# ESP-WROOM-32-Breakout.net
KiCad netlist of a schematic drawn in EAGLE
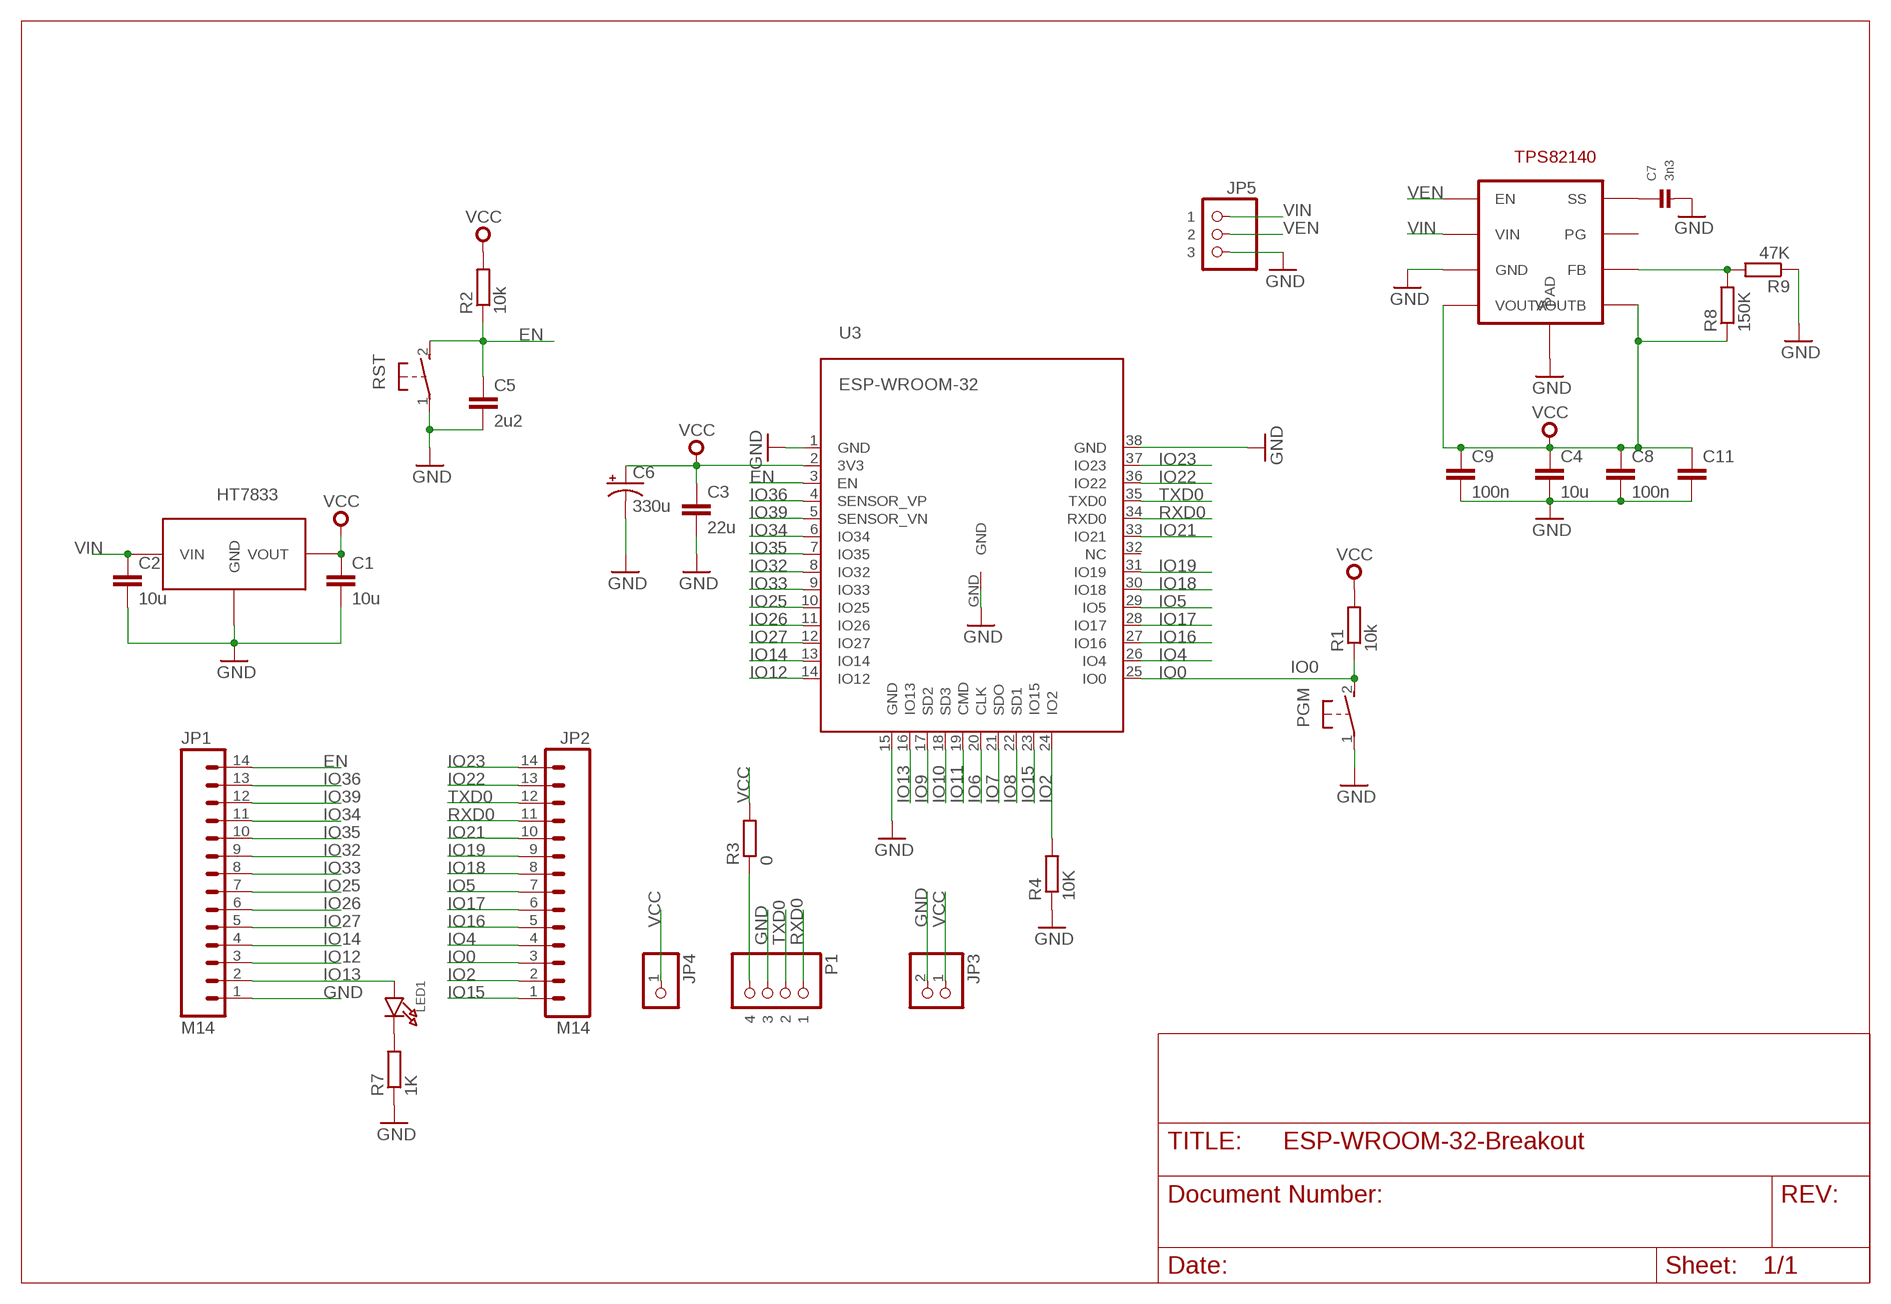
[diagram p0: schematic, sheet 1]

(export (version "E")
  (design (tool "Eeschema 10.0.6"))
  (components
    (comp (ref "C1")
      (value "10u")
      (footprint "eagle-import:C0603")
      (libsource (lib "eagle-import") (part "C-EUC0603"))
    )
    (comp (ref "C2")
      (value "10u")
      (footprint "eagle-import:C0603")
      (libsource (lib "eagle-import") (part "C-EUC0603"))
    )
    (comp (ref "C3")
      (value "22u")
      (footprint "eagle-import:0805")
      (libsource (lib "eagle-import") (part "CAP0805"))
    )
    (comp (ref "C4")
      (value "10u")
      (footprint "eagle-import:C0603")
      (libsource (lib "eagle-import") (part "C-EUC0603"))
    )
    (comp (ref "C5")
      (value "2u2")
      (footprint "eagle-import:C0603")
      (libsource (lib "eagle-import") (part "C-EUC0603"))
    )
    (comp (ref "C6")
      (value "330u")
      (footprint "eagle-import:VISHAY_C")
      (libsource (lib "eagle-import") (part "CAP_POLSMD"))
    )
    (comp (ref "C7")
      (value "3n3")
      (footprint "eagle-import:0603")
      (libsource (lib "eagle-import") (part "CAP_CERAMIC0603"))
    )
    (comp (ref "C8")
      (value "100n")
      (footprint "eagle-import:C0603")
      (libsource (lib "eagle-import") (part "C-EUC0603"))
    )
    (comp (ref "C9")
      (value "100n")
      (footprint "eagle-import:C0603")
      (libsource (lib "eagle-import") (part "C-EUC0603"))
    )
    (comp (ref "C11")
      (value "CAPSMD")
      (footprint "eagle-import:GRM43D")
      (libsource (lib "eagle-import") (part "CAPSMD"))
    )
    (comp (ref "JP1")
      (value "M14")
      (footprint "eagle-import:1X14")
      (libsource (lib "eagle-import") (part "M14"))
    )
    (comp (ref "JP2")
      (value "M14")
      (footprint "eagle-import:1X14")
      (libsource (lib "eagle-import") (part "M14"))
    )
    (comp (ref "JP3")
      (value "HEADER-1X2ROUND")
      (footprint "eagle-import:1X02_ROUND")
      (libsource (lib "eagle-import") (part "HEADER-1X2ROUND"))
    )
    (comp (ref "JP4")
      (value "HEADER-1X1ROUND")
      (footprint "eagle-import:1X01_ROUND")
      (libsource (lib "eagle-import") (part "HEADER-1X1ROUND"))
    )
    (comp (ref "JP5")
      (value "HEADER-1X3ROUND")
      (footprint "eagle-import:1X03_ROUND")
      (libsource (lib "eagle-import") (part "HEADER-1X3ROUND"))
    )
    (comp (ref "LED1")
      (value "LED0603")
      (footprint "eagle-import:CHIPLED_0603")
      (libsource (lib "eagle-import") (part "LED0603"))
    )
    (comp (ref "P1")
      (value "HEADER-1X4ROUND")
      (footprint "eagle-import:1X04_ROUND")
      (libsource (lib "eagle-import") (part "HEADER-1X4ROUND"))
    )
    (comp (ref "PGM")
      (value "DTSM-3")
      (footprint "eagle-import:DTSM-3")
      (libsource (lib "eagle-import") (part "DTSM-3"))
    )
    (comp (ref "R1")
      (value "10k")
      (footprint "eagle-import:R0603")
      (libsource (lib "eagle-import") (part "R-EU_R0603"))
    )
    (comp (ref "R2")
      (value "10k")
      (footprint "eagle-import:R0603")
      (libsource (lib "eagle-import") (part "R-EU_R0603"))
    )
    (comp (ref "R3")
      (value "0")
      (footprint "eagle-import:R0603")
      (libsource (lib "eagle-import") (part "R-EU_R0603"))
    )
    (comp (ref "R4")
      (value "10K")
      (footprint "eagle-import:R0603")
      (libsource (lib "eagle-import") (part "R-EU_R0603"))
    )
    (comp (ref "R7")
      (value "1K")
      (footprint "eagle-import:R0603")
      (libsource (lib "eagle-import") (part "R-EU_R0603"))
    )
    (comp (ref "R8")
      (value "150K")
      (footprint "eagle-import:R0603")
      (libsource (lib "eagle-import") (part "R-EU_R0603"))
    )
    (comp (ref "R9")
      (value "47K")
      (footprint "eagle-import:R0603")
      (libsource (lib "eagle-import") (part "R-EU_R0603"))
    )
    (comp (ref "RST")
      (value "DTSM-3")
      (footprint "eagle-import:DTSM-3")
      (libsource (lib "eagle-import") (part "DTSM-3"))
    )
    (comp (ref "U$1")
      (value "HT7833")
      (footprint "eagle-import:SOT89")
      (libsource (lib "eagle-import") (part "HT7333"))
    )
    (comp (ref "U$2")
      (value "TPS82140")
      (footprint "eagle-import:TPS82140")
      (libsource (lib "eagle-import") (part "TPS82140"))
    )
    (comp (ref "U3")
      (value "ESP-WROOM-32")
      (footprint "eagle-import:ESP-WROOM-32")
      (libsource (lib "eagle-import") (part "ESP-WROOM-32"))
    )
  )
  (nets
    (net (code "1") (name "/EN") (class "Default")
      (node (ref "C5") (pin "1") (pinfunction "1_1") (pintype "passive"))
      (node (ref "JP1") (pin "14") (pinfunction "14_14") (pintype "passive"))
      (node (ref "R2") (pin "1") (pinfunction "1_1") (pintype "passive"))
      (node (ref "RST") (pin "2") (pinfunction "2_2") (pintype "passive"))
      (node (ref "U3") (pin "3") (pinfunction "EN_3") (pintype "bidirectional"))
    )
    (net (code "2") (name "/IO0") (class "Default")
      (node (ref "JP2") (pin "3") (pinfunction "3_3") (pintype "passive"))
      (node (ref "PGM") (pin "2") (pinfunction "2_2") (pintype "passive"))
      (node (ref "R1") (pin "1") (pinfunction "1_1") (pintype "passive"))
      (node (ref "U3") (pin "25") (pinfunction "IO0_25") (pintype "bidirectional"))
    )
    (net (code "3") (name "/IO2") (class "Default")
      (node (ref "JP2") (pin "2") (pinfunction "2_2") (pintype "passive"))
      (node (ref "R4") (pin "2") (pinfunction "2_2") (pintype "passive"))
      (node (ref "U3") (pin "24") (pinfunction "IO2_24") (pintype "bidirectional"))
    )
    (net (code "4") (name "/IO4") (class "Default")
      (node (ref "JP2") (pin "4") (pinfunction "4_4") (pintype "passive"))
      (node (ref "U3") (pin "26") (pinfunction "IO4_26") (pintype "bidirectional"))
    )
    (net (code "5") (name "/IO5") (class "Default")
      (node (ref "JP2") (pin "7") (pinfunction "7_7") (pintype "passive"))
      (node (ref "U3") (pin "29") (pinfunction "IO5_29") (pintype "bidirectional"))
    )
    (net (code "6") (name "/IO6") (class "Default")
      (node (ref "U3") (pin "20") (pinfunction "CLK_20") (pintype "bidirectional"))
    )
    (net (code "7") (name "/IO7") (class "Default")
      (node (ref "U3") (pin "21") (pinfunction "SDO_21") (pintype "bidirectional"))
    )
    (net (code "8") (name "/IO8") (class "Default")
      (node (ref "U3") (pin "22") (pinfunction "SD1_22") (pintype "bidirectional"))
    )
    (net (code "9") (name "/IO9") (class "Default")
      (node (ref "U3") (pin "17") (pinfunction "SD2_17") (pintype "bidirectional"))
    )
    (net (code "10") (name "/IO10") (class "Default")
      (node (ref "U3") (pin "18") (pinfunction "SD3_18") (pintype "bidirectional"))
    )
    (net (code "11") (name "/IO11") (class "Default")
      (node (ref "U3") (pin "19") (pinfunction "CMD_19") (pintype "bidirectional"))
    )
    (net (code "12") (name "/IO12") (class "Default")
      (node (ref "JP1") (pin "3") (pinfunction "3_3") (pintype "passive"))
      (node (ref "U3") (pin "14") (pinfunction "IO12_14") (pintype "bidirectional"))
    )
    (net (code "13") (name "/IO13") (class "Default")
      (node (ref "JP1") (pin "2") (pinfunction "2_2") (pintype "passive"))
      (node (ref "LED1") (pin "A") (pinfunction "A_A") (pintype "passive"))
      (node (ref "U3") (pin "16") (pinfunction "IO13_16") (pintype "bidirectional"))
    )
    (net (code "14") (name "/IO14") (class "Default")
      (node (ref "JP1") (pin "4") (pinfunction "4_4") (pintype "passive"))
      (node (ref "U3") (pin "13") (pinfunction "IO14_13") (pintype "bidirectional"))
    )
    (net (code "15") (name "/IO15") (class "Default")
      (node (ref "JP2") (pin "1") (pinfunction "1_1") (pintype "passive"))
      (node (ref "U3") (pin "23") (pinfunction "IO15_23") (pintype "bidirectional"))
    )
    (net (code "16") (name "/IO16") (class "Default")
      (node (ref "JP2") (pin "5") (pinfunction "5_5") (pintype "passive"))
      (node (ref "U3") (pin "27") (pinfunction "IO16_27") (pintype "bidirectional"))
    )
    (net (code "17") (name "/IO17") (class "Default")
      (node (ref "JP2") (pin "6") (pinfunction "6_6") (pintype "passive"))
      (node (ref "U3") (pin "28") (pinfunction "IO17_28") (pintype "bidirectional"))
    )
    (net (code "18") (name "/IO18") (class "Default")
      (node (ref "JP2") (pin "8") (pinfunction "8_8") (pintype "passive"))
      (node (ref "U3") (pin "30") (pinfunction "IO18_30") (pintype "bidirectional"))
    )
    (net (code "19") (name "/IO19") (class "Default")
      (node (ref "JP2") (pin "9") (pinfunction "9_9") (pintype "passive"))
      (node (ref "U3") (pin "31") (pinfunction "IO19_31") (pintype "bidirectional"))
    )
    (net (code "20") (name "/IO21") (class "Default")
      (node (ref "JP2") (pin "10") (pinfunction "10_10") (pintype "passive"))
      (node (ref "U3") (pin "33") (pinfunction "IO21_33") (pintype "bidirectional"))
    )
    (net (code "21") (name "/IO22") (class "Default")
      (node (ref "JP2") (pin "13") (pinfunction "13_13") (pintype "passive"))
      (node (ref "U3") (pin "36") (pinfunction "IO22_36") (pintype "bidirectional"))
    )
    (net (code "22") (name "/IO23") (class "Default")
      (node (ref "JP2") (pin "14") (pinfunction "14_14") (pintype "passive"))
      (node (ref "U3") (pin "37") (pinfunction "IO23_37") (pintype "bidirectional"))
    )
    (net (code "23") (name "/IO25") (class "Default")
      (node (ref "JP1") (pin "7") (pinfunction "7_7") (pintype "passive"))
      (node (ref "U3") (pin "10") (pinfunction "IO25_10") (pintype "bidirectional"))
    )
    (net (code "24") (name "/IO26") (class "Default")
      (node (ref "JP1") (pin "6") (pinfunction "6_6") (pintype "passive"))
      (node (ref "U3") (pin "11") (pinfunction "IO26_11") (pintype "bidirectional"))
    )
    (net (code "25") (name "/IO27") (class "Default")
      (node (ref "JP1") (pin "5") (pinfunction "5_5") (pintype "passive"))
      (node (ref "U3") (pin "12") (pinfunction "IO27_12") (pintype "bidirectional"))
    )
    (net (code "26") (name "/IO32") (class "Default")
      (node (ref "JP1") (pin "9") (pinfunction "9_9") (pintype "passive"))
      (node (ref "U3") (pin "8") (pinfunction "IO32_8") (pintype "bidirectional"))
    )
    (net (code "27") (name "/IO33") (class "Default")
      (node (ref "JP1") (pin "8") (pinfunction "8_8") (pintype "passive"))
      (node (ref "U3") (pin "9") (pinfunction "IO33_9") (pintype "bidirectional"))
    )
    (net (code "28") (name "/IO34") (class "Default")
      (node (ref "JP1") (pin "11") (pinfunction "11_11") (pintype "passive"))
      (node (ref "U3") (pin "6") (pinfunction "IO34_6") (pintype "bidirectional"))
    )
    (net (code "29") (name "/IO35") (class "Default")
      (node (ref "JP1") (pin "10") (pinfunction "10_10") (pintype "passive"))
      (node (ref "U3") (pin "7") (pinfunction "IO35_7") (pintype "bidirectional"))
    )
    (net (code "30") (name "/IO36") (class "Default")
      (node (ref "JP1") (pin "13") (pinfunction "13_13") (pintype "passive"))
      (node (ref "U3") (pin "4") (pinfunction "SENSOR_VP_4") (pintype "bidirectional"))
    )
    (net (code "31") (name "/IO39") (class "Default")
      (node (ref "JP1") (pin "12") (pinfunction "12_12") (pintype "passive"))
      (node (ref "U3") (pin "5") (pinfunction "SENSOR_VN_5") (pintype "bidirectional"))
    )
    (net (code "32") (name "/RXD0") (class "Default")
      (node (ref "JP2") (pin "11") (pinfunction "11_11") (pintype "passive"))
      (node (ref "P1") (pin "1") (pinfunction "1_1") (pintype "passive"))
      (node (ref "U3") (pin "34") (pinfunction "RXD0_34") (pintype "bidirectional"))
    )
    (net (code "33") (name "/TXD0") (class "Default")
      (node (ref "JP2") (pin "12") (pinfunction "12_12") (pintype "passive"))
      (node (ref "P1") (pin "2") (pinfunction "2_2") (pintype "passive"))
      (node (ref "U3") (pin "35") (pinfunction "TXD0_35") (pintype "bidirectional"))
    )
    (net (code "34") (name "/VEN") (class "Default")
      (node (ref "JP5") (pin "2") (pinfunction "2_2") (pintype "passive"))
      (node (ref "U$2") (pin "P$1") (pinfunction "EN_P$1") (pintype "bidirectional"))
    )
    (net (code "35") (name "/VIN") (class "Default")
      (node (ref "C2") (pin "1") (pinfunction "1_1") (pintype "passive"))
      (node (ref "JP5") (pin "1") (pinfunction "1_1") (pintype "passive"))
      (node (ref "U$1") (pin "VIN") (pinfunction "VIN_VIN") (pintype "bidirectional"))
      (node (ref "U$2") (pin "P$2") (pinfunction "VIN_P$2") (pintype "bidirectional"))
    )
    (net (code "36") (name "GND") (class "Default")
      (node (ref "C1") (pin "2") (pinfunction "2_2") (pintype "passive"))
      (node (ref "C11") (pin "C") (pinfunction "2_C") (pintype "passive"))
      (node (ref "C2") (pin "2") (pinfunction "2_2") (pintype "passive"))
      (node (ref "C3") (pin "2") (pinfunction "2_2") (pintype "passive"))
      (node (ref "C4") (pin "2") (pinfunction "2_2") (pintype "passive"))
      (node (ref "C5") (pin "2") (pinfunction "2_2") (pintype "passive"))
      (node (ref "C6") (pin "-") (pinfunction "-_-") (pintype "passive"))
      (node (ref "C7") (pin "2") (pinfunction "P$2_2") (pintype "passive"))
      (node (ref "C8") (pin "2") (pinfunction "2_2") (pintype "passive"))
      (node (ref "C9") (pin "2") (pinfunction "2_2") (pintype "passive"))
      (node (ref "JP1") (pin "1") (pinfunction "1_1") (pintype "passive"))
      (node (ref "JP3") (pin "2") (pinfunction "2_2") (pintype "passive"))
      (node (ref "JP5") (pin "3") (pinfunction "3_3") (pintype "passive"))
      (node (ref "P1") (pin "3") (pinfunction "3_3") (pintype "passive"))
      (node (ref "PGM") (pin "1") (pinfunction "1_1") (pintype "passive"))
      (node (ref "R4") (pin "1") (pinfunction "1_1") (pintype "passive"))
      (node (ref "R7") (pin "1") (pinfunction "1_1") (pintype "passive"))
      (node (ref "R9") (pin "1") (pinfunction "1_1") (pintype "passive"))
      (node (ref "RST") (pin "1") (pinfunction "1_1") (pintype "passive"))
      (node (ref "U$1") (pin "GND") (pinfunction "GND_GND") (pintype "bidirectional"))
      (node (ref "U$2") (pin "P$3") (pinfunction "GND_P$3") (pintype "bidirectional"))
      (node (ref "U$2") (pin "P$9") (pinfunction "PAD_P$9") (pintype "bidirectional"))
      (node (ref "U3") (pin "1") (pinfunction "GND_1") (pintype "bidirectional"))
      (node (ref "U3") (pin "15") (pinfunction "GND_15") (pintype "bidirectional"))
      (node (ref "U3") (pin "38") (pinfunction "GND_38") (pintype "bidirectional"))
      (node (ref "U3") (pin "GND") (pinfunction "GND_GND") (pintype "bidirectional"))
    )
    (net (code "37") (name "Net-(C7-P$1)") (class "Default")
      (node (ref "C7") (pin "1") (pinfunction "P$1_1") (pintype "passive"))
      (node (ref "U$2") (pin "P$8") (pinfunction "SS_P$8") (pintype "bidirectional"))
    )
    (net (code "38") (name "Net-(LED1-PadC)") (class "Default")
      (node (ref "LED1") (pin "C") (pinfunction "C_C") (pintype "passive"))
      (node (ref "R7") (pin "2") (pinfunction "2_2") (pintype "passive"))
    )
    (net (code "39") (name "Net-(P1-Pad4)") (class "Default")
      (node (ref "P1") (pin "4") (pinfunction "4_4") (pintype "passive"))
      (node (ref "R3") (pin "1") (pinfunction "1_1") (pintype "passive"))
    )
    (net (code "40") (name "Net-(U$2-FB)") (class "Default")
      (node (ref "R8") (pin "2") (pinfunction "2_2") (pintype "passive"))
      (node (ref "R9") (pin "2") (pinfunction "2_2") (pintype "passive"))
      (node (ref "U$2") (pin "P$6") (pinfunction "FB_P$6") (pintype "bidirectional"))
    )
    (net (code "41") (name "VCC") (class "Default")
      (node (ref "C1") (pin "1") (pinfunction "1_1") (pintype "passive"))
      (node (ref "C11") (pin "A") (pinfunction "1_A") (pintype "passive"))
      (node (ref "C3") (pin "1") (pinfunction "1_1") (pintype "passive"))
      (node (ref "C4") (pin "1") (pinfunction "1_1") (pintype "passive"))
      (node (ref "C6") (pin "+") (pinfunction "+_+") (pintype "passive"))
      (node (ref "C8") (pin "1") (pinfunction "1_1") (pintype "passive"))
      (node (ref "C9") (pin "1") (pinfunction "1_1") (pintype "passive"))
      (node (ref "JP3") (pin "1") (pinfunction "1_1") (pintype "passive"))
      (node (ref "JP4") (pin "1") (pinfunction "1_1") (pintype "passive"))
      (node (ref "R1") (pin "2") (pinfunction "2_2") (pintype "passive"))
      (node (ref "R2") (pin "2") (pinfunction "2_2") (pintype "passive"))
      (node (ref "R3") (pin "2") (pinfunction "2_2") (pintype "passive"))
      (node (ref "R8") (pin "1") (pinfunction "1_1") (pintype "passive"))
      (node (ref "U$1") (pin "VOUT") (pinfunction "VOUT_VOUT") (pintype "bidirectional"))
      (node (ref "U$2") (pin "P$4") (pinfunction "VOUTA_P$4") (pintype "bidirectional"))
      (node (ref "U$2") (pin "P$5") (pinfunction "VOUTB_P$5") (pintype "bidirectional"))
      (node (ref "U3") (pin "2") (pinfunction "3V3_2") (pintype "bidirectional"))
    )
    (net (code "42") (name "unconnected-(U$2-PG-PadP$7)") (class "Default")
      (node (ref "U$2") (pin "P$7") (pinfunction "PG_P$7") (pintype "bidirectional"))
    )
    (net (code "43") (name "unconnected-(U3-NC-Pad32)") (class "Default")
      (node (ref "U3") (pin "32") (pinfunction "NC_32") (pintype "bidirectional"))
    )
  )
)
